# SCH_Placa_Peixebinha_2026-07-04.net
KiCad netlist of a schematic drawn in EasyEDA
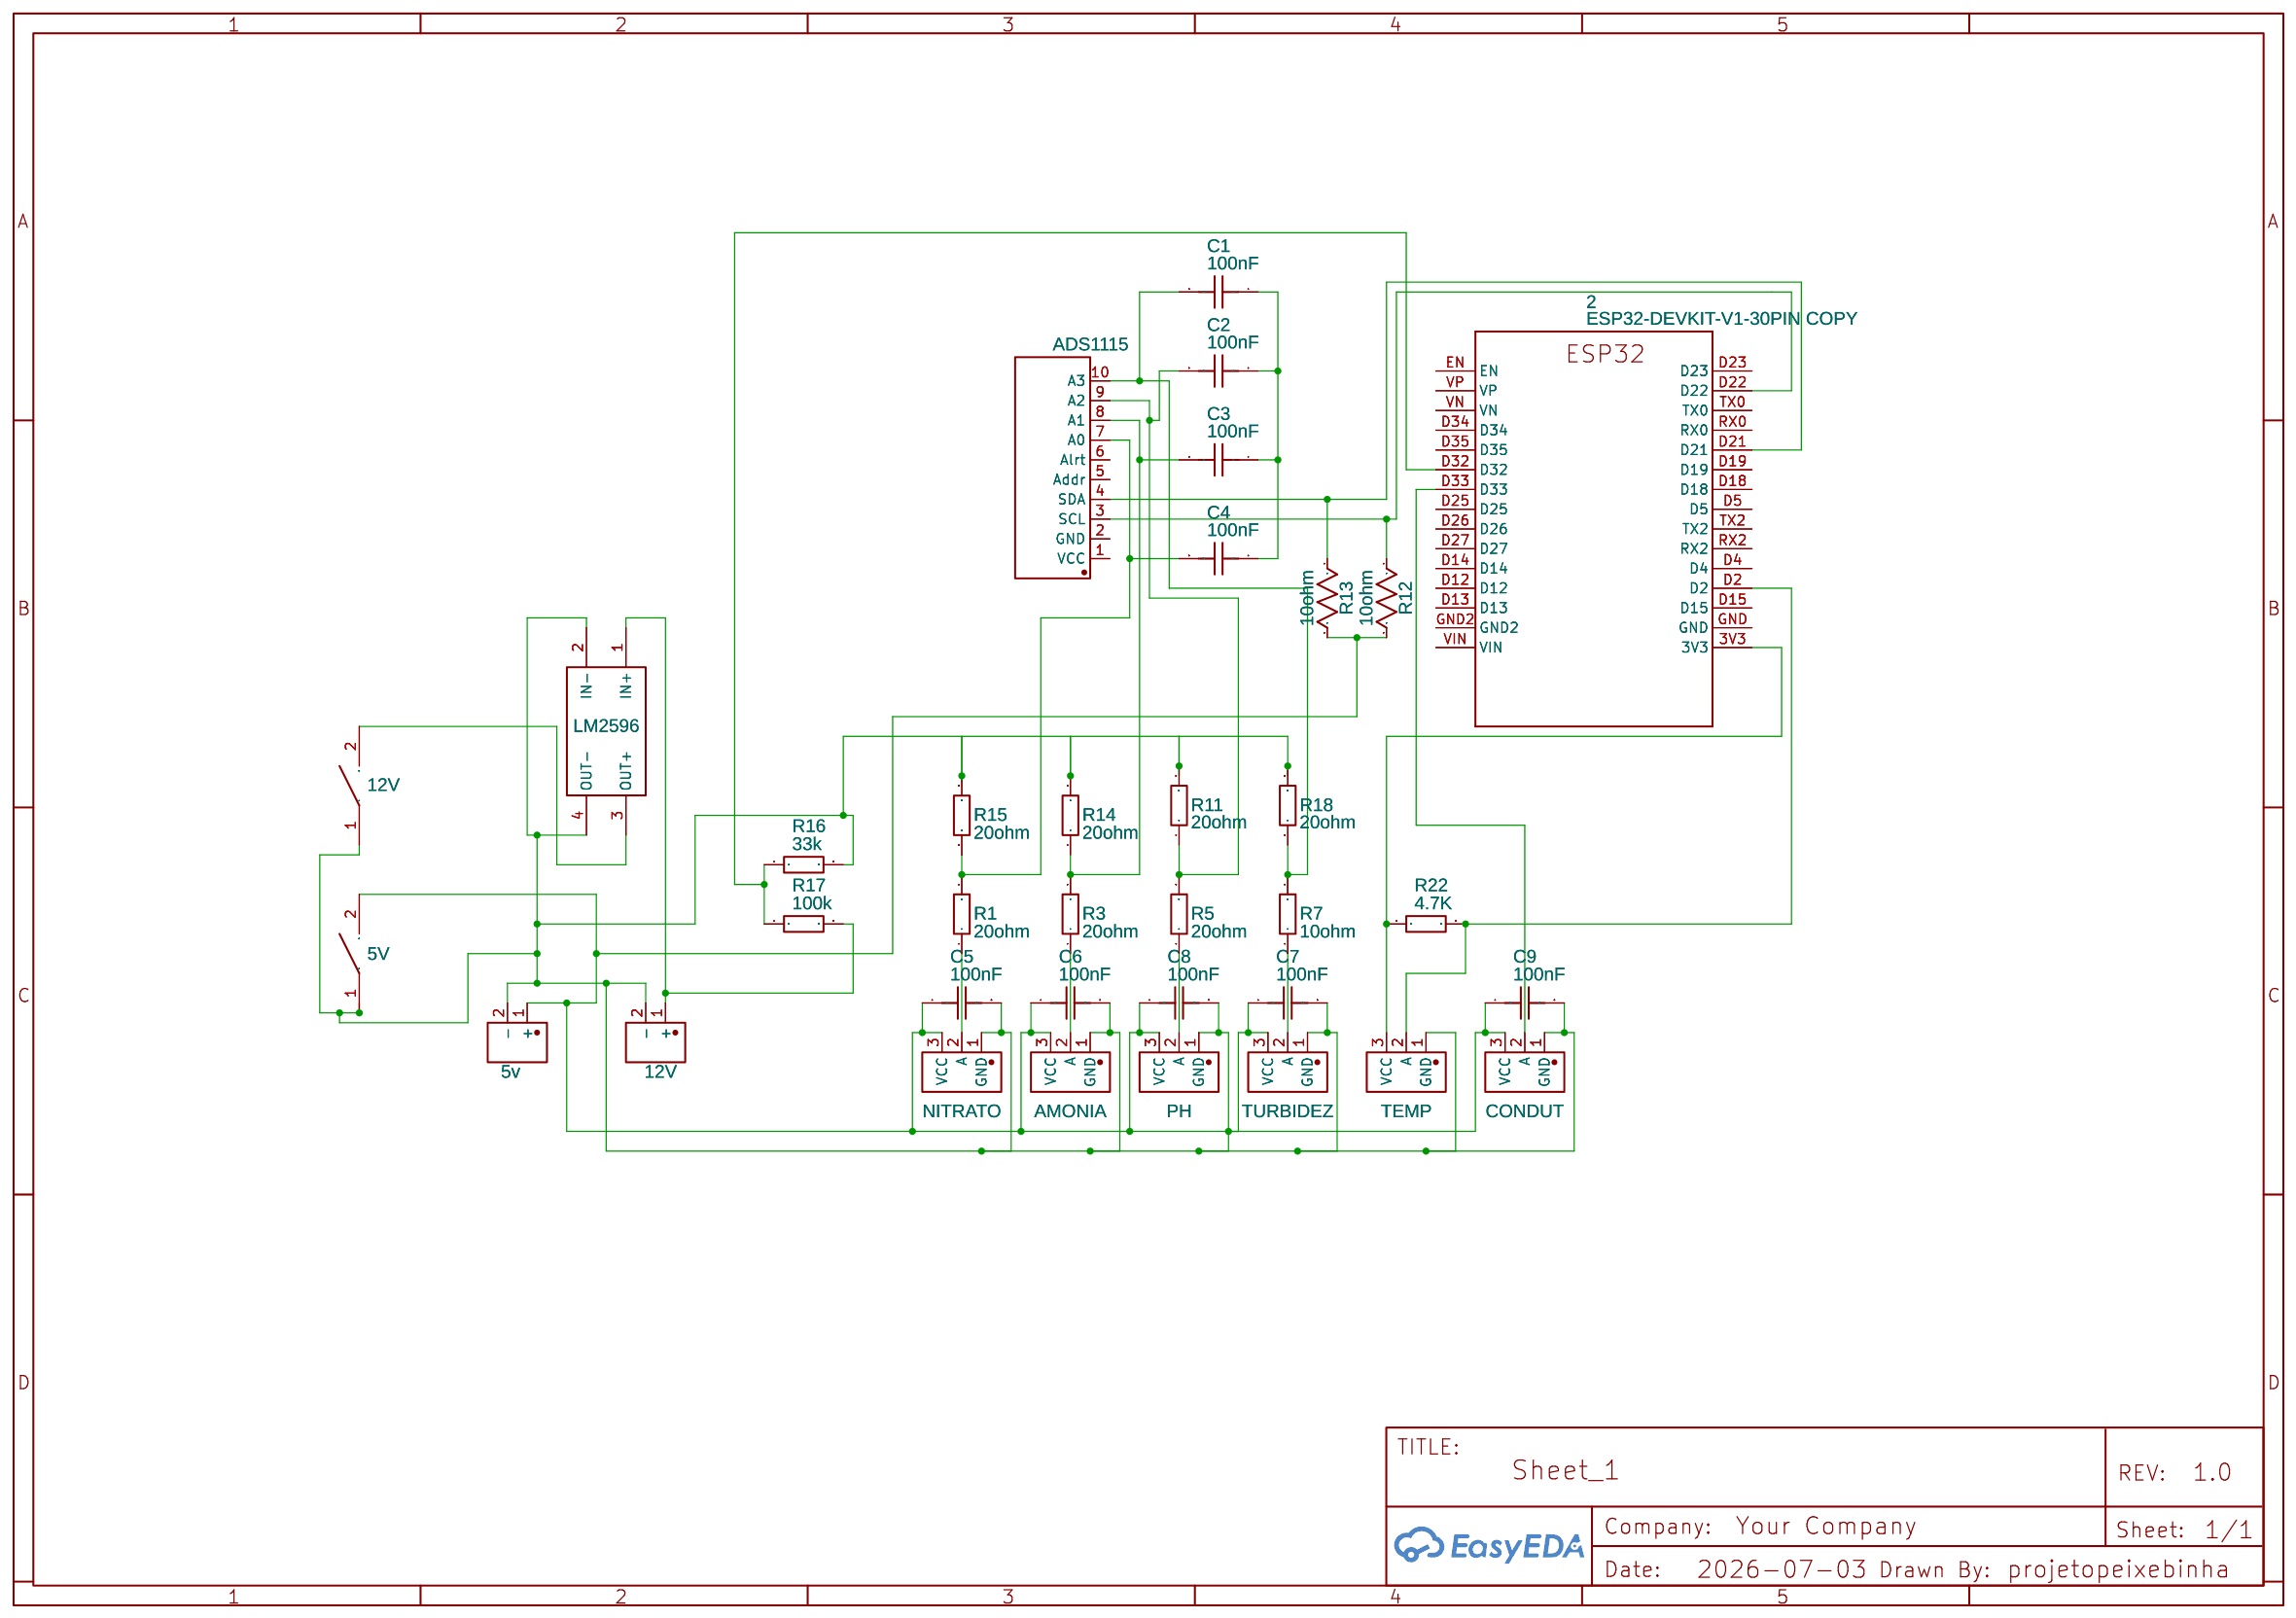
[diagram p0: schematic sheet]

(export (version "E")
  (design (tool "Eeschema 10.0.6"))
  (components
    (comp (ref "2") (value "ESP32-DEVKIT-V1-30PIN COPY") (libsource (lib "") (part "ESP32-DEVKIT-V1-30PIN")))
    (comp (ref "5V") (value "5V") (libsource (lib "") (part "DIP_SWITCH_1_WAY")))
    (comp (ref "12V") (value "5V") (libsource (lib "") (part "DIP_SWITCH_1_WAY_1")))
    (comp (ref "AMO") (value "AMONIA") (libsource (lib "") (part "BORNERA 3P_SERGIO")))
    (comp (ref "BORNE1") (value "5v") (libsource (lib "") (part "BORNERA 2P")))
    (comp (ref "BORNE2") (value "12V") (libsource (lib "") (part "BORNERA 2P")))
    (comp (ref "C1") (value "100nF") (libsource (lib "") (part "C_RAD-0.3_US")))
    (comp (ref "C2") (value "100nF") (libsource (lib "") (part "C_RAD-0.3_US")))
    (comp (ref "C3") (value "100nF") (libsource (lib "") (part "C_RAD-0.3_US")))
    (comp (ref "C4") (value "100nF") (libsource (lib "") (part "C_RAD-0.3_US")))
    (comp (ref "C5") (value "100nF") (libsource (lib "") (part "C_RAD-0.3_US_1")))
    (comp (ref "C6") (value "100nF") (libsource (lib "") (part "C_RAD-0.3_US_1")))
    (comp (ref "C7") (value "100nF") (libsource (lib "") (part "C_RAD-0.3_US_1")))
    (comp (ref "C8") (value "100nF") (libsource (lib "") (part "C_RAD-0.3_US_1")))
    (comp (ref "C9") (value "100nF") (libsource (lib "") (part "C_RAD-0.3_US_1")))
    (comp (ref "COND") (value "CONDUT") (libsource (lib "") (part "BORNERA 3P_SERGIO_2")))
    (comp (ref "NIT") (value "NITRATO") (libsource (lib "") (part "BORNERA 3P_SERGIO_4")))
    (comp (ref "PH") (value "PH") (libsource (lib "") (part "BORNERA 3P_SERGIO_1")))
    (comp (ref "R1")
      (value "20ohm")
      (fields
        (field (name "Manufacturer Part") "EWWR0001J20R0T9")
        (field (name "Manufacturer") "ResistorToday")
      )
      (libsource (lib "") (part "RESISTOR 1/2 W"))
    )
    (comp (ref "R3")
      (value "20ohm")
      (fields
        (field (name "Manufacturer Part") "EWWR0001J20R0T9")
        (field (name "Manufacturer") "ResistorToday")
      )
      (libsource (lib "") (part "RESISTOR 1/2 W"))
    )
    (comp (ref "R5")
      (value "20ohm")
      (fields
        (field (name "Manufacturer Part") "EWWR0001J20R0T9")
        (field (name "Manufacturer") "ResistorToday")
      )
      (libsource (lib "") (part "RESISTOR 1/2 W"))
    )
    (comp (ref "R7")
      (value "10ohm")
      (fields
        (field (name "Manufacturer Part") "EWWR0001J20R0T9")
        (field (name "Manufacturer") "ResistorToday")
      )
      (libsource (lib "") (part "RESISTOR 1/2 W"))
    )
    (comp (ref "R11")
      (value "20ohm")
      (fields
        (field (name "Manufacturer Part") "EWWR0001J20R0T9")
        (field (name "Manufacturer") "ResistorToday")
      )
      (libsource (lib "") (part "RESISTOR 1/2 W"))
    )
    (comp (ref "R12") (value "10ohm") (libsource (lib "") (part "R_0603_US")))
    (comp (ref "R13") (value "10ohm") (libsource (lib "") (part "R_0603_US")))
    (comp (ref "R14")
      (value "20ohm")
      (fields
        (field (name "Manufacturer Part") "EWWR0001J20R0T9")
        (field (name "Manufacturer") "ResistorToday")
      )
      (libsource (lib "") (part "RESISTOR 1/2 W"))
    )
    (comp (ref "R15")
      (value "20ohm")
      (fields
        (field (name "Manufacturer Part") "EWWR0001J20R0T9")
        (field (name "Manufacturer") "ResistorToday")
      )
      (libsource (lib "") (part "RESISTOR 1/2 W"))
    )
    (comp (ref "R16")
      (value "33k")
      (fields
        (field (name "Manufacturer Part") "EWWR0001J20R0T9")
        (field (name "Manufacturer") "ResistorToday")
      )
      (libsource (lib "") (part "RESISTOR 1/2 W_1"))
    )
    (comp (ref "R17")
      (value "100k")
      (fields
        (field (name "Manufacturer Part") "EWWR0001J20R0T9")
        (field (name "Manufacturer") "ResistorToday")
      )
      (libsource (lib "") (part "RESISTOR 1/2 W_1"))
    )
    (comp (ref "R18")
      (value "20ohm")
      (fields
        (field (name "Manufacturer Part") "EWWR0001J20R0T9")
        (field (name "Manufacturer") "ResistorToday")
      )
      (libsource (lib "") (part "RESISTOR 1/2 W"))
    )
    (comp (ref "R22")
      (value "4.7K")
      (fields
        (field (name "Manufacturer Part") "EWWR0001J20R0T9")
        (field (name "Manufacturer") "ResistorToday")
      )
      (libsource (lib "") (part "RESISTOR 1/2 W_1"))
    )
    (comp (ref "TEMP") (value "TEMP") (libsource (lib "") (part "BORNERA 3P_SERGIO_3")))
    (comp (ref "TURB") (value "TURBIDEZ") (libsource (lib "") (part "BORNERA 3P_SERGIO_5")))
    (comp (ref "U1") (value "ADS1115") (libsource (lib "") (part "ADS1115_F")))
    (comp (ref "U3") (value "LM2596") (libsource (lib "") (part "BuckConverters_LM2596_Adj")))
  )
  (nets
    (net (code "1") (name "Net-(2-PadD32)") (class "Default")
      (node (ref "2") (pin "D32") (pinfunction "D32_D32") (pintype "unspecified"))
      (node (ref "R16") (pin "1") (pinfunction "1_1") (pintype "unspecified"))
      (node (ref "R17") (pin "1") (pinfunction "1_1") (pintype "unspecified"))
    )
    (net (code "2") (name "Net-(AMO-A)") (class "Default")
      (node (ref "AMO") (pin "2") (pinfunction "A_2") (pintype "unspecified"))
      (node (ref "R3") (pin "1") (pinfunction "1_1") (pintype "unspecified"))
    )
    (net (code "3") (name "Net-(AMO-GND)") (class "Default")
      (node (ref "12V") (pin "1") (pinfunction "1_1") (pintype "unspecified"))
      (node (ref "5V") (pin "1") (pinfunction "1_1") (pintype "unspecified"))
      (node (ref "5V") (pin "2") (pinfunction "2_2") (pintype "unspecified"))
      (node (ref "AMO") (pin "1") (pinfunction "GND_1") (pintype "unspecified"))
      (node (ref "AMO") (pin "3") (pinfunction "VCC_3") (pintype "unspecified"))
      (node (ref "BORNE1") (pin "1") (pinfunction "+_1") (pintype "unspecified"))
      (node (ref "BORNE1") (pin "2") (pinfunction "-_2") (pintype "unspecified"))
      (node (ref "BORNE2") (pin "2") (pinfunction "-_2") (pintype "unspecified"))
      (node (ref "C5") (pin "1") (pinfunction "1_1") (pintype "unspecified"))
      (node (ref "C5") (pin "2") (pinfunction "2_2") (pintype "unspecified"))
      (node (ref "C6") (pin "1") (pinfunction "1_1") (pintype "unspecified"))
      (node (ref "C6") (pin "2") (pinfunction "2_2") (pintype "unspecified"))
      (node (ref "C7") (pin "1") (pinfunction "1_1") (pintype "unspecified"))
      (node (ref "C7") (pin "2") (pinfunction "2_2") (pintype "unspecified"))
      (node (ref "C8") (pin "1") (pinfunction "1_1") (pintype "unspecified"))
      (node (ref "C8") (pin "2") (pinfunction "2_2") (pintype "unspecified"))
      (node (ref "C9") (pin "1") (pinfunction "1_1") (pintype "unspecified"))
      (node (ref "C9") (pin "2") (pinfunction "2_2") (pintype "unspecified"))
      (node (ref "COND") (pin "1") (pinfunction "GND_1") (pintype "unspecified"))
      (node (ref "COND") (pin "3") (pinfunction "VCC_3") (pintype "unspecified"))
      (node (ref "NIT") (pin "1") (pinfunction "GND_1") (pintype "unspecified"))
      (node (ref "NIT") (pin "3") (pinfunction "VCC_3") (pintype "unspecified"))
      (node (ref "PH") (pin "1") (pinfunction "GND_1") (pintype "unspecified"))
      (node (ref "PH") (pin "3") (pinfunction "VCC_3") (pintype "unspecified"))
      (node (ref "R11") (pin "2") (pinfunction "2_2") (pintype "unspecified"))
      (node (ref "R12") (pin "2") (pinfunction "2_2") (pintype "unspecified"))
      (node (ref "R13") (pin "2") (pinfunction "2_2") (pintype "unspecified"))
      (node (ref "R14") (pin "2") (pinfunction "2_2") (pintype "unspecified"))
      (node (ref "R15") (pin "2") (pinfunction "2_2") (pintype "unspecified"))
      (node (ref "R16") (pin "2") (pinfunction "2_2") (pintype "unspecified"))
      (node (ref "R18") (pin "2") (pinfunction "2_2") (pintype "unspecified"))
      (node (ref "TEMP") (pin "1") (pinfunction "GND_1") (pintype "unspecified"))
      (node (ref "TURB") (pin "1") (pinfunction "GND_1") (pintype "unspecified"))
      (node (ref "TURB") (pin "3") (pinfunction "VCC_3") (pintype "unspecified"))
      (node (ref "U3") (pin "2") (pinfunction "IN-_2") (pintype "unspecified"))
      (node (ref "U3") (pin "4") (pinfunction "OUT-_4") (pintype "unspecified"))
    )
    (net (code "4") (name "Net-(BORNE2-+)") (class "Default")
      (node (ref "BORNE2") (pin "1") (pinfunction "+_1") (pintype "unspecified"))
      (node (ref "R17") (pin "2") (pinfunction "2_2") (pintype "unspecified"))
      (node (ref "U3") (pin "1") (pinfunction "IN+_1") (pintype "unspecified"))
    )
    (net (code "5") (name "Net-(C1-Pad1)") (class "Default")
      (node (ref "C1") (pin "1") (pinfunction "1_1") (pintype "unspecified"))
      (node (ref "C2") (pin "1") (pinfunction "1_1") (pintype "unspecified"))
      (node (ref "C3") (pin "1") (pinfunction "1_1") (pintype "unspecified"))
      (node (ref "C4") (pin "1") (pinfunction "1_1") (pintype "unspecified"))
    )
    (net (code "6") (name "Net-(COND-A)") (class "Default")
      (node (ref "2") (pin "D33") (pinfunction "D33_D33") (pintype "unspecified"))
      (node (ref "COND") (pin "2") (pinfunction "A_2") (pintype "unspecified"))
    )
    (net (code "7") (name "Net-(NIT-A)") (class "Default")
      (node (ref "NIT") (pin "2") (pinfunction "A_2") (pintype "unspecified"))
      (node (ref "R1") (pin "1") (pinfunction "1_1") (pintype "unspecified"))
    )
    (net (code "8") (name "Net-(PH-A)") (class "Default")
      (node (ref "PH") (pin "2") (pinfunction "A_2") (pintype "unspecified"))
      (node (ref "R5") (pin "1") (pinfunction "1_1") (pintype "unspecified"))
    )
    (net (code "9") (name "Net-(TEMP-A)") (class "Default")
      (node (ref "2") (pin "D2") (pinfunction "D2_D2") (pintype "unspecified"))
      (node (ref "R22") (pin "2") (pinfunction "2_2") (pintype "unspecified"))
      (node (ref "TEMP") (pin "2") (pinfunction "A_2") (pintype "unspecified"))
    )
    (net (code "10") (name "Net-(TEMP-VCC)") (class "Default")
      (node (ref "2") (pin "3V3") (pinfunction "3V3_3V3") (pintype "unspecified"))
      (node (ref "R22") (pin "1") (pinfunction "1_1") (pintype "unspecified"))
      (node (ref "TEMP") (pin "3") (pinfunction "VCC_3") (pintype "unspecified"))
    )
    (net (code "11") (name "Net-(TURB-A)") (class "Default")
      (node (ref "R7") (pin "1") (pinfunction "1_1") (pintype "unspecified"))
      (node (ref "TURB") (pin "2") (pinfunction "A_2") (pintype "unspecified"))
    )
    (net (code "12") (name "Net-(U1-A0)") (class "Default")
      (node (ref "C4") (pin "2") (pinfunction "2_2") (pintype "unspecified"))
      (node (ref "R1") (pin "2") (pinfunction "2_2") (pintype "unspecified"))
      (node (ref "R15") (pin "1") (pinfunction "1_1") (pintype "unspecified"))
      (node (ref "U1") (pin "7") (pinfunction "A0_7") (pintype "unspecified"))
    )
    (net (code "13") (name "Net-(U1-A1)") (class "Default")
      (node (ref "C3") (pin "2") (pinfunction "2_2") (pintype "unspecified"))
      (node (ref "R14") (pin "1") (pinfunction "1_1") (pintype "unspecified"))
      (node (ref "R3") (pin "2") (pinfunction "2_2") (pintype "unspecified"))
      (node (ref "U1") (pin "8") (pinfunction "A1_8") (pintype "unspecified"))
    )
    (net (code "14") (name "Net-(U1-A2)") (class "Default")
      (node (ref "C2") (pin "2") (pinfunction "2_2") (pintype "unspecified"))
      (node (ref "R11") (pin "1") (pinfunction "1_1") (pintype "unspecified"))
      (node (ref "R5") (pin "2") (pinfunction "2_2") (pintype "unspecified"))
      (node (ref "U1") (pin "9") (pinfunction "A2_9") (pintype "unspecified"))
    )
    (net (code "15") (name "Net-(U1-A3)") (class "Default")
      (node (ref "C1") (pin "2") (pinfunction "2_2") (pintype "unspecified"))
      (node (ref "R18") (pin "1") (pinfunction "1_1") (pintype "unspecified"))
      (node (ref "R7") (pin "2") (pinfunction "2_2") (pintype "unspecified"))
      (node (ref "U1") (pin "10") (pinfunction "A3_10") (pintype "unspecified"))
    )
    (net (code "16") (name "Net-(U1-SCL)") (class "Default")
      (node (ref "2") (pin "D22") (pinfunction "D22_D22") (pintype "unspecified"))
      (node (ref "R12") (pin "1") (pinfunction "1_1") (pintype "unspecified"))
      (node (ref "U1") (pin "3") (pinfunction "SCL_3") (pintype "unspecified"))
    )
    (net (code "17") (name "Net-(U1-SDA)") (class "Default")
      (node (ref "2") (pin "D21") (pinfunction "D21_D21") (pintype "unspecified"))
      (node (ref "R13") (pin "1") (pinfunction "1_1") (pintype "unspecified"))
      (node (ref "U1") (pin "4") (pinfunction "SDA_4") (pintype "unspecified"))
    )
    (net (code "18") (name "Net-(U3-OUT+)") (class "Default")
      (node (ref "12V") (pin "2") (pinfunction "2_2") (pintype "unspecified"))
      (node (ref "U3") (pin "3") (pinfunction "OUT+_3") (pintype "unspecified"))
    )
    (net (code "19") (name "unconnected-(2-PadD4)") (class "Default")
      (node (ref "2") (pin "D4") (pinfunction "D4_D4") (pintype "unspecified"))
    )
    (net (code "20") (name "unconnected-(2-PadD5)") (class "Default")
      (node (ref "2") (pin "D5") (pinfunction "D5_D5") (pintype "unspecified"))
    )
    (net (code "21") (name "unconnected-(2-PadD12)") (class "Default")
      (node (ref "2") (pin "D12") (pinfunction "D12_D12") (pintype "unspecified"))
    )
    (net (code "22") (name "unconnected-(2-PadD13)") (class "Default")
      (node (ref "2") (pin "D13") (pinfunction "D13_D13") (pintype "unspecified"))
    )
    (net (code "23") (name "unconnected-(2-PadD14)") (class "Default")
      (node (ref "2") (pin "D14") (pinfunction "D14_D14") (pintype "unspecified"))
    )
    (net (code "24") (name "unconnected-(2-PadD15)") (class "Default")
      (node (ref "2") (pin "D15") (pinfunction "D15_D15") (pintype "unspecified"))
    )
    (net (code "25") (name "unconnected-(2-PadD18)") (class "Default")
      (node (ref "2") (pin "D18") (pinfunction "D18_D18") (pintype "unspecified"))
    )
    (net (code "26") (name "unconnected-(2-PadD19)") (class "Default")
      (node (ref "2") (pin "D19") (pinfunction "D19_D19") (pintype "unspecified"))
    )
    (net (code "27") (name "unconnected-(2-PadD23)") (class "Default")
      (node (ref "2") (pin "D23") (pinfunction "D23_D23") (pintype "unspecified"))
    )
    (net (code "28") (name "unconnected-(2-PadD25)") (class "Default")
      (node (ref "2") (pin "D25") (pinfunction "D25_D25") (pintype "unspecified"))
    )
    (net (code "29") (name "unconnected-(2-PadD26)") (class "Default")
      (node (ref "2") (pin "D26") (pinfunction "D26_D26") (pintype "unspecified"))
    )
    (net (code "30") (name "unconnected-(2-PadD27)") (class "Default")
      (node (ref "2") (pin "D27") (pinfunction "D27_D27") (pintype "unspecified"))
    )
    (net (code "31") (name "unconnected-(2-PadD34)") (class "Default")
      (node (ref "2") (pin "D34") (pinfunction "D34_D34") (pintype "unspecified"))
    )
    (net (code "32") (name "unconnected-(2-PadD35)") (class "Default")
      (node (ref "2") (pin "D35") (pinfunction "D35_D35") (pintype "unspecified"))
    )
    (net (code "33") (name "unconnected-(2-PadEN)") (class "Default")
      (node (ref "2") (pin "EN") (pinfunction "EN_EN") (pintype "unspecified"))
    )
    (net (code "34") (name "unconnected-(2-PadGND)") (class "Default")
      (node (ref "2") (pin "GND") (pinfunction "GND_GND") (pintype "unspecified"))
    )
    (net (code "35") (name "unconnected-(2-PadGND2)") (class "Default")
      (node (ref "2") (pin "GND2") (pinfunction "GND2_GND2") (pintype "unspecified"))
    )
    (net (code "36") (name "unconnected-(2-PadRX0)") (class "Default")
      (node (ref "2") (pin "RX0") (pinfunction "RX0_RX0") (pintype "unspecified"))
    )
    (net (code "37") (name "unconnected-(2-PadRX2)") (class "Default")
      (node (ref "2") (pin "RX2") (pinfunction "RX2_RX2") (pintype "unspecified"))
    )
    (net (code "38") (name "unconnected-(2-PadTX0)") (class "Default")
      (node (ref "2") (pin "TX0") (pinfunction "TX0_TX0") (pintype "unspecified"))
    )
    (net (code "39") (name "unconnected-(2-PadTX2)") (class "Default")
      (node (ref "2") (pin "TX2") (pinfunction "TX2_TX2") (pintype "unspecified"))
    )
    (net (code "40") (name "unconnected-(2-PadVIN)") (class "Default")
      (node (ref "2") (pin "VIN") (pinfunction "VIN_VIN") (pintype "unspecified"))
    )
    (net (code "41") (name "unconnected-(2-PadVN)") (class "Default")
      (node (ref "2") (pin "VN") (pinfunction "VN_VN") (pintype "unspecified"))
    )
    (net (code "42") (name "unconnected-(2-PadVP)") (class "Default")
      (node (ref "2") (pin "VP") (pinfunction "VP_VP") (pintype "unspecified"))
    )
    (net (code "43") (name "unconnected-(U1-Addr-Pad5)") (class "Default")
      (node (ref "U1") (pin "5") (pinfunction "Addr_5") (pintype "unspecified"))
    )
    (net (code "44") (name "unconnected-(U1-Alrt-Pad6)") (class "Default")
      (node (ref "U1") (pin "6") (pinfunction "Alrt_6") (pintype "unspecified"))
    )
    (net (code "45") (name "unconnected-(U1-GND-Pad2)") (class "Default")
      (node (ref "U1") (pin "2") (pinfunction "GND_2") (pintype "unspecified"))
    )
    (net (code "46") (name "unconnected-(U1-VCC-Pad1)") (class "Default")
      (node (ref "U1") (pin "1") (pinfunction "VCC_1") (pintype "unspecified"))
    )
  )
)
